# esp12_led_improved.net
KiCad netlist of a schematic drawn in EAGLE
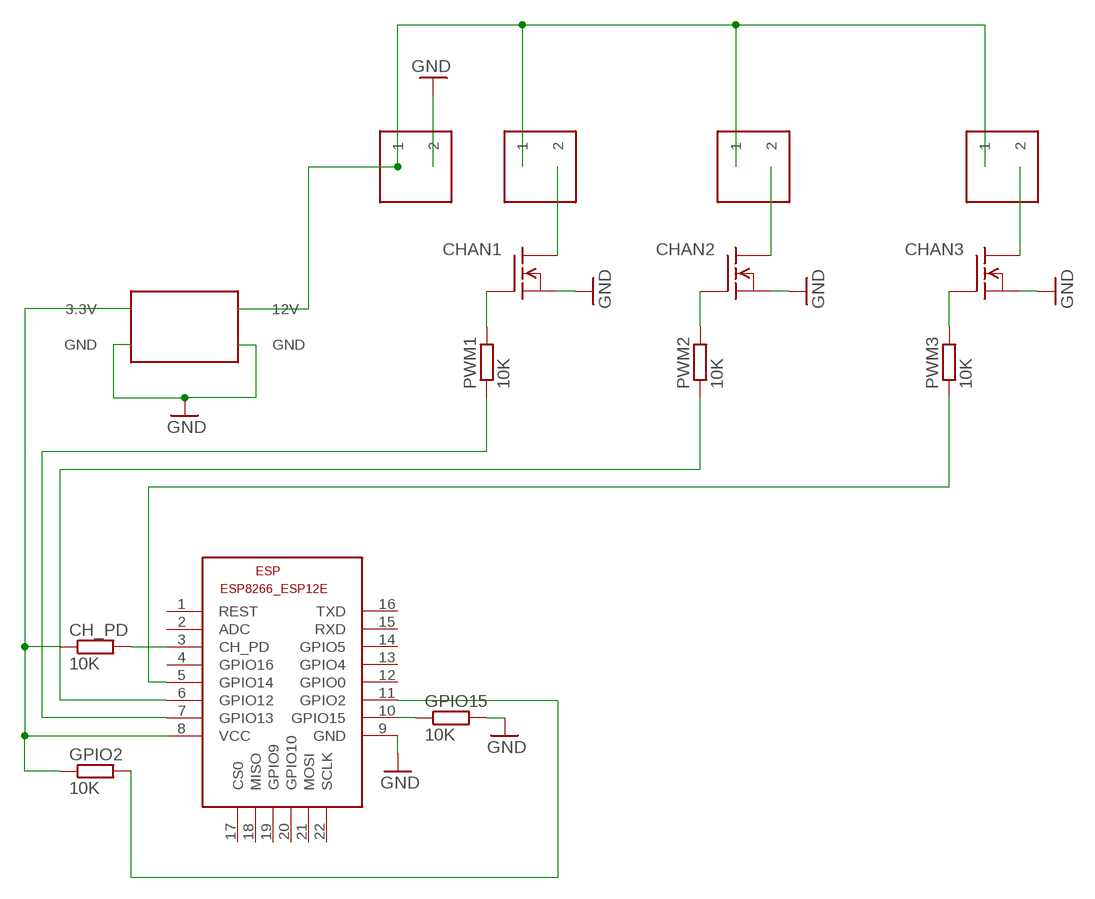
[diagram p0: schematic, sheet 1]

(export (version "E")
  (design (tool "Eeschema 10.0.6"))
  (components
    (comp (ref "CHAN1")
      (value "FDS5680")
      (footprint "eagle-import:SO-8")
      (libsource (lib "eagle-import") (part "FDS5680"))
    )
    (comp (ref "CHAN2")
      (value "FDS5680")
      (footprint "eagle-import:SO-8")
      (libsource (lib "eagle-import") (part "FDS5680"))
    )
    (comp (ref "CHAN3")
      (value "FDS5680")
      (footprint "eagle-import:SO-8")
      (libsource (lib "eagle-import") (part "FDS5680"))
    )
    (comp (ref "CH_PD")
      (value "10K")
      (footprint "eagle-import:R0603")
      (libsource (lib "eagle-import") (part "R-EU_R0603"))
    )
    (comp (ref "ESP")
      (value "ESP8266-12EESP8266-ESP12E")
      (footprint "eagle-import:ESP8266-ESP12E")
      (libsource (lib "eagle-import") (part "ESP8266-12EESP8266-ESP12E"))
    )
    (comp (ref "GPIO2")
      (value "10K")
      (footprint "eagle-import:R0603")
      (libsource (lib "eagle-import") (part "R-EU_R0603"))
    )
    (comp (ref "GPIO15")
      (value "10K")
      (footprint "eagle-import:R0603")
      (libsource (lib "eagle-import") (part "R-EU_R0603"))
    )
    (comp (ref "OUT1")
      (value "KF350-P2")
      (footprint "eagle-import:KF350-2P")
      (libsource (lib "eagle-import") (part "KF350-P2"))
    )
    (comp (ref "OUT2")
      (value "KF350-P2")
      (footprint "eagle-import:KF350-2P")
      (libsource (lib "eagle-import") (part "KF350-P2"))
    )
    (comp (ref "OUT3")
      (value "KF350-P2")
      (footprint "eagle-import:KF350-2P")
      (libsource (lib "eagle-import") (part "KF350-P2"))
    )
    (comp (ref "PWM1")
      (value "10K")
      (footprint "eagle-import:R0603")
      (libsource (lib "eagle-import") (part "R-EU_R0603"))
    )
    (comp (ref "PWM2")
      (value "10K")
      (footprint "eagle-import:R0603")
      (libsource (lib "eagle-import") (part "R-EU_R0603"))
    )
    (comp (ref "PWM3")
      (value "10K")
      (footprint "eagle-import:R0603")
      (libsource (lib "eagle-import") (part "R-EU_R0603"))
    )
    (comp (ref "PWR1")
      (value "MP2307-MINI-360")
      (footprint "eagle-import:MP2307-MINI-360")
      (libsource (lib "eagle-import") (part "MP2307-MINI-360"))
    )
    (comp (ref "PWR_IN")
      (value "KF350-P2")
      (footprint "eagle-import:KF350-2P")
      (libsource (lib "eagle-import") (part "KF350-P2"))
    )
  )
  (nets
    (net (code "1") (name "GND") (class "Default")
      (node (ref "CHAN1") (pin "1") (pinfunction "S_1") (pintype "passive"))
      (node (ref "CHAN1") (pin "2") (pinfunction "S_2") (pintype "passive"))
      (node (ref "CHAN1") (pin "3") (pinfunction "S_3") (pintype "passive"))
      (node (ref "CHAN2") (pin "1") (pinfunction "S_1") (pintype "passive"))
      (node (ref "CHAN2") (pin "2") (pinfunction "S_2") (pintype "passive"))
      (node (ref "CHAN2") (pin "3") (pinfunction "S_3") (pintype "passive"))
      (node (ref "CHAN3") (pin "1") (pinfunction "S_1") (pintype "passive"))
      (node (ref "CHAN3") (pin "2") (pinfunction "S_2") (pintype "passive"))
      (node (ref "CHAN3") (pin "3") (pinfunction "S_3") (pintype "passive"))
      (node (ref "ESP") (pin "9") (pinfunction "GND_9") (pintype "bidirectional"))
      (node (ref "GPIO15") (pin "2") (pinfunction "2_2") (pintype "passive"))
      (node (ref "PWR1") (pin "GND@1") (pinfunction "GND_GND@1") (pintype "power_in"))
      (node (ref "PWR1") (pin "GND@2") (pinfunction "GND_GND@2") (pintype "power_in"))
      (node (ref "PWR_IN") (pin "2") (pinfunction "2_2") (pintype "bidirectional"))
    )
    (net (code "2") (name "Net-(CHAN1-D-Pad5)") (class "Default")
      (node (ref "CHAN1") (pin "5") (pinfunction "D_5") (pintype "passive"))
      (node (ref "CHAN1") (pin "6") (pinfunction "D_6") (pintype "passive"))
      (node (ref "CHAN1") (pin "7") (pinfunction "D_7") (pintype "passive"))
      (node (ref "CHAN1") (pin "8") (pinfunction "D_8") (pintype "passive"))
      (node (ref "OUT1") (pin "2") (pinfunction "2_2") (pintype "bidirectional"))
    )
    (net (code "3") (name "Net-(CHAN1-G)") (class "Default")
      (node (ref "CHAN1") (pin "4") (pinfunction "G_4") (pintype "passive"))
      (node (ref "PWM1") (pin "2") (pinfunction "2_2") (pintype "passive"))
    )
    (net (code "4") (name "Net-(CHAN2-D-Pad5)") (class "Default")
      (node (ref "CHAN2") (pin "5") (pinfunction "D_5") (pintype "passive"))
      (node (ref "CHAN2") (pin "6") (pinfunction "D_6") (pintype "passive"))
      (node (ref "CHAN2") (pin "7") (pinfunction "D_7") (pintype "passive"))
      (node (ref "CHAN2") (pin "8") (pinfunction "D_8") (pintype "passive"))
      (node (ref "OUT2") (pin "2") (pinfunction "2_2") (pintype "bidirectional"))
    )
    (net (code "5") (name "Net-(CHAN2-G)") (class "Default")
      (node (ref "CHAN2") (pin "4") (pinfunction "G_4") (pintype "passive"))
      (node (ref "PWM2") (pin "2") (pinfunction "2_2") (pintype "passive"))
    )
    (net (code "6") (name "Net-(CHAN3-D-Pad5)") (class "Default")
      (node (ref "CHAN3") (pin "5") (pinfunction "D_5") (pintype "passive"))
      (node (ref "CHAN3") (pin "6") (pinfunction "D_6") (pintype "passive"))
      (node (ref "CHAN3") (pin "7") (pinfunction "D_7") (pintype "passive"))
      (node (ref "CHAN3") (pin "8") (pinfunction "D_8") (pintype "passive"))
      (node (ref "OUT3") (pin "2") (pinfunction "2_2") (pintype "bidirectional"))
    )
    (net (code "7") (name "Net-(CHAN3-G)") (class "Default")
      (node (ref "CHAN3") (pin "4") (pinfunction "G_4") (pintype "passive"))
      (node (ref "PWM3") (pin "2") (pinfunction "2_2") (pintype "passive"))
    )
    (net (code "8") (name "Net-(ESP-CH_PD)") (class "Default")
      (node (ref "CH_PD") (pin "2") (pinfunction "2_2") (pintype "passive"))
      (node (ref "ESP") (pin "3") (pinfunction "CH_PD_3") (pintype "bidirectional"))
    )
    (net (code "9") (name "Net-(ESP-GPIO2)") (class "Default")
      (node (ref "ESP") (pin "11") (pinfunction "GPIO2_11") (pintype "bidirectional"))
      (node (ref "GPIO2") (pin "2") (pinfunction "2_2") (pintype "passive"))
    )
    (net (code "10") (name "Net-(ESP-GPIO12)") (class "Default")
      (node (ref "ESP") (pin "6") (pinfunction "GPIO12_6") (pintype "bidirectional"))
      (node (ref "PWM2") (pin "1") (pinfunction "1_1") (pintype "passive"))
    )
    (net (code "11") (name "Net-(ESP-GPIO13)") (class "Default")
      (node (ref "ESP") (pin "7") (pinfunction "GPIO13_7") (pintype "bidirectional"))
      (node (ref "PWM1") (pin "1") (pinfunction "1_1") (pintype "passive"))
    )
    (net (code "12") (name "Net-(ESP-GPIO14)") (class "Default")
      (node (ref "ESP") (pin "5") (pinfunction "GPIO14_5") (pintype "bidirectional"))
      (node (ref "PWM3") (pin "1") (pinfunction "1_1") (pintype "passive"))
    )
    (net (code "13") (name "Net-(ESP-GPIO15)") (class "Default")
      (node (ref "ESP") (pin "10") (pinfunction "GPIO15_10") (pintype "bidirectional"))
      (node (ref "GPIO15") (pin "1") (pinfunction "1_1") (pintype "passive"))
    )
    (net (code "14") (name "Net-(ESP-VCC)") (class "Default")
      (node (ref "CH_PD") (pin "1") (pinfunction "1_1") (pintype "passive"))
      (node (ref "ESP") (pin "8") (pinfunction "VCC_8") (pintype "bidirectional"))
      (node (ref "GPIO2") (pin "1") (pinfunction "1_1") (pintype "passive"))
      (node (ref "PWR1") (pin "3.3V") (pinfunction "3.3V_3.3V") (pintype "power_in"))
    )
    (net (code "15") (name "Net-(OUT1-Pad1)") (class "Default")
      (node (ref "OUT1") (pin "1") (pinfunction "1_1") (pintype "bidirectional"))
      (node (ref "OUT2") (pin "1") (pinfunction "1_1") (pintype "bidirectional"))
      (node (ref "OUT3") (pin "1") (pinfunction "1_1") (pintype "bidirectional"))
      (node (ref "PWR1") (pin "12V") (pinfunction "12V_12V") (pintype "power_in"))
      (node (ref "PWR_IN") (pin "1") (pinfunction "1_1") (pintype "bidirectional"))
    )
    (net (code "16") (name "unconnected-(ESP-ADC-Pad2)") (class "Default")
      (node (ref "ESP") (pin "2") (pinfunction "ADC_2") (pintype "bidirectional"))
    )
    (net (code "17") (name "unconnected-(ESP-CS0-Pad17)") (class "Default")
      (node (ref "ESP") (pin "17") (pinfunction "CS0_17") (pintype "bidirectional"))
    )
    (net (code "18") (name "unconnected-(ESP-GPIO0-Pad12)") (class "Default")
      (node (ref "ESP") (pin "12") (pinfunction "GPIO0_12") (pintype "bidirectional"))
    )
    (net (code "19") (name "unconnected-(ESP-GPIO4-Pad13)") (class "Default")
      (node (ref "ESP") (pin "13") (pinfunction "GPIO4_13") (pintype "bidirectional"))
    )
    (net (code "20") (name "unconnected-(ESP-GPIO5-Pad14)") (class "Default")
      (node (ref "ESP") (pin "14") (pinfunction "GPIO5_14") (pintype "bidirectional"))
    )
    (net (code "21") (name "unconnected-(ESP-GPIO9-Pad19)") (class "Default")
      (node (ref "ESP") (pin "19") (pinfunction "GPIO9_19") (pintype "bidirectional"))
    )
    (net (code "22") (name "unconnected-(ESP-GPIO10-Pad20)") (class "Default")
      (node (ref "ESP") (pin "20") (pinfunction "GPIO10_20") (pintype "bidirectional"))
    )
    (net (code "23") (name "unconnected-(ESP-GPIO16-Pad4)") (class "Default")
      (node (ref "ESP") (pin "4") (pinfunction "GPIO16_4") (pintype "bidirectional"))
    )
    (net (code "24") (name "unconnected-(ESP-MISO-Pad18)") (class "Default")
      (node (ref "ESP") (pin "18") (pinfunction "MISO_18") (pintype "bidirectional"))
    )
    (net (code "25") (name "unconnected-(ESP-MOSI-Pad21)") (class "Default")
      (node (ref "ESP") (pin "21") (pinfunction "MOSI_21") (pintype "bidirectional"))
    )
    (net (code "26") (name "unconnected-(ESP-REST-Pad1)") (class "Default")
      (node (ref "ESP") (pin "1") (pinfunction "REST_1") (pintype "bidirectional"))
    )
    (net (code "27") (name "unconnected-(ESP-RXD-Pad15)") (class "Default")
      (node (ref "ESP") (pin "15") (pinfunction "RXD_15") (pintype "bidirectional"))
    )
    (net (code "28") (name "unconnected-(ESP-SCLK-Pad22)") (class "Default")
      (node (ref "ESP") (pin "22") (pinfunction "SCLK_22") (pintype "bidirectional"))
    )
    (net (code "29") (name "unconnected-(ESP-TXD-Pad16)") (class "Default")
      (node (ref "ESP") (pin "16") (pinfunction "TXD_16") (pintype "bidirectional"))
    )
  )
)
